# eeZee_Crystal.net
KiCad netlist of a schematic drawn in EAGLE
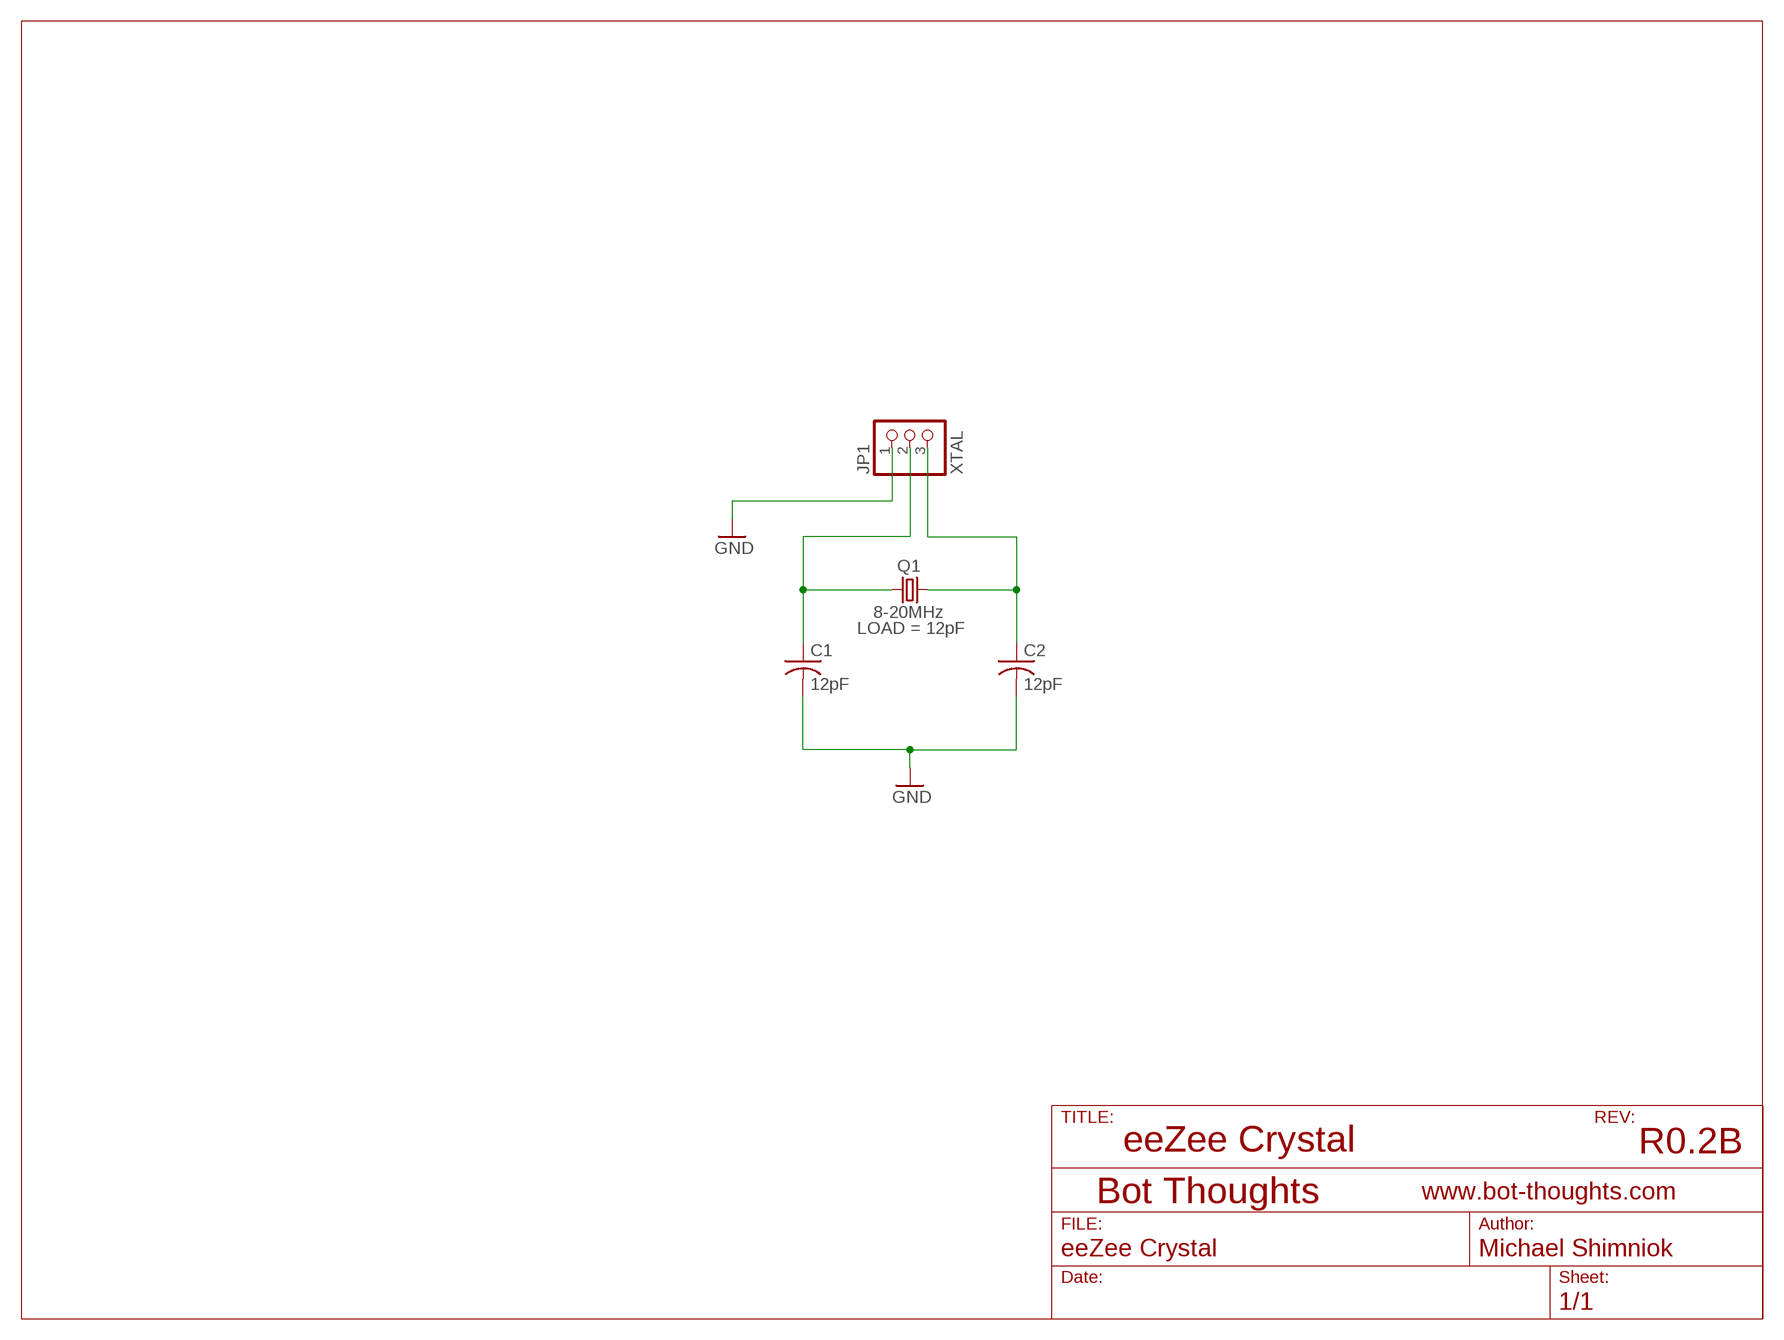
[diagram p0: schematic, sheet 1]

(export (version "E")
  (design (tool "Eeschema 10.0.6"))
  (components
    (comp (ref "C1")
      (value "12pF")
      (footprint "eagle-import:C0603")
      (fields (field (name "PARTNO") "C1608C0G1H080D"))
      (libsource (lib "eagle-import") (part "C-USC0603"))
    )
    (comp (ref "C2")
      (value "12pF")
      (footprint "eagle-import:C0603")
      (fields (field (name "PARTNO") "C1608C0G1H080D"))
      (libsource (lib "eagle-import") (part "C-USC0603"))
    )
    (comp (ref "JP1")
      (value "XTAL")
      (footprint "eagle-import:1X03-S")
      (libsource (lib "eagle-import") (part "PINHD-1X03_2.54-S"))
    )
    (comp (ref "Q1")
      (value "8-20MHz")
      (footprint "eagle-import:NDK_2PAD_5X3")
      (fields (field (name "LOAD") "12pF") (field (name "PARTNO") "NX5032GA-16.000000MHZ-LN-CD-1"))
      (libsource (lib "eagle-import") (part "CRYSTALNDK5X3"))
    )
  )
  (nets
    (net (code "1") (name "GND") (class "Default")
      (node (ref "C1") (pin "2") (pinfunction "2_2") (pintype "passive"))
      (node (ref "C2") (pin "2") (pinfunction "2_2") (pintype "passive"))
      (node (ref "JP1") (pin "1") (pinfunction "1_1") (pintype "passive"))
    )
    (net (code "2") (name "Net-(Q1-1)") (class "Default")
      (node (ref "C2") (pin "1") (pinfunction "1_1") (pintype "passive"))
      (node (ref "JP1") (pin "3") (pinfunction "3_3") (pintype "passive"))
      (node (ref "Q1") (pin "P$1") (pinfunction "1_P$1") (pintype "passive"))
    )
    (net (code "3") (name "Net-(Q1-2)") (class "Default")
      (node (ref "C1") (pin "1") (pinfunction "1_1") (pintype "passive"))
      (node (ref "JP1") (pin "2") (pinfunction "2_2") (pintype "passive"))
      (node (ref "Q1") (pin "P$2") (pinfunction "2_P$2") (pintype "passive"))
    )
  )
)
